# stm32hw03.net
KiCad netlist of a schematic drawn in EAGLE
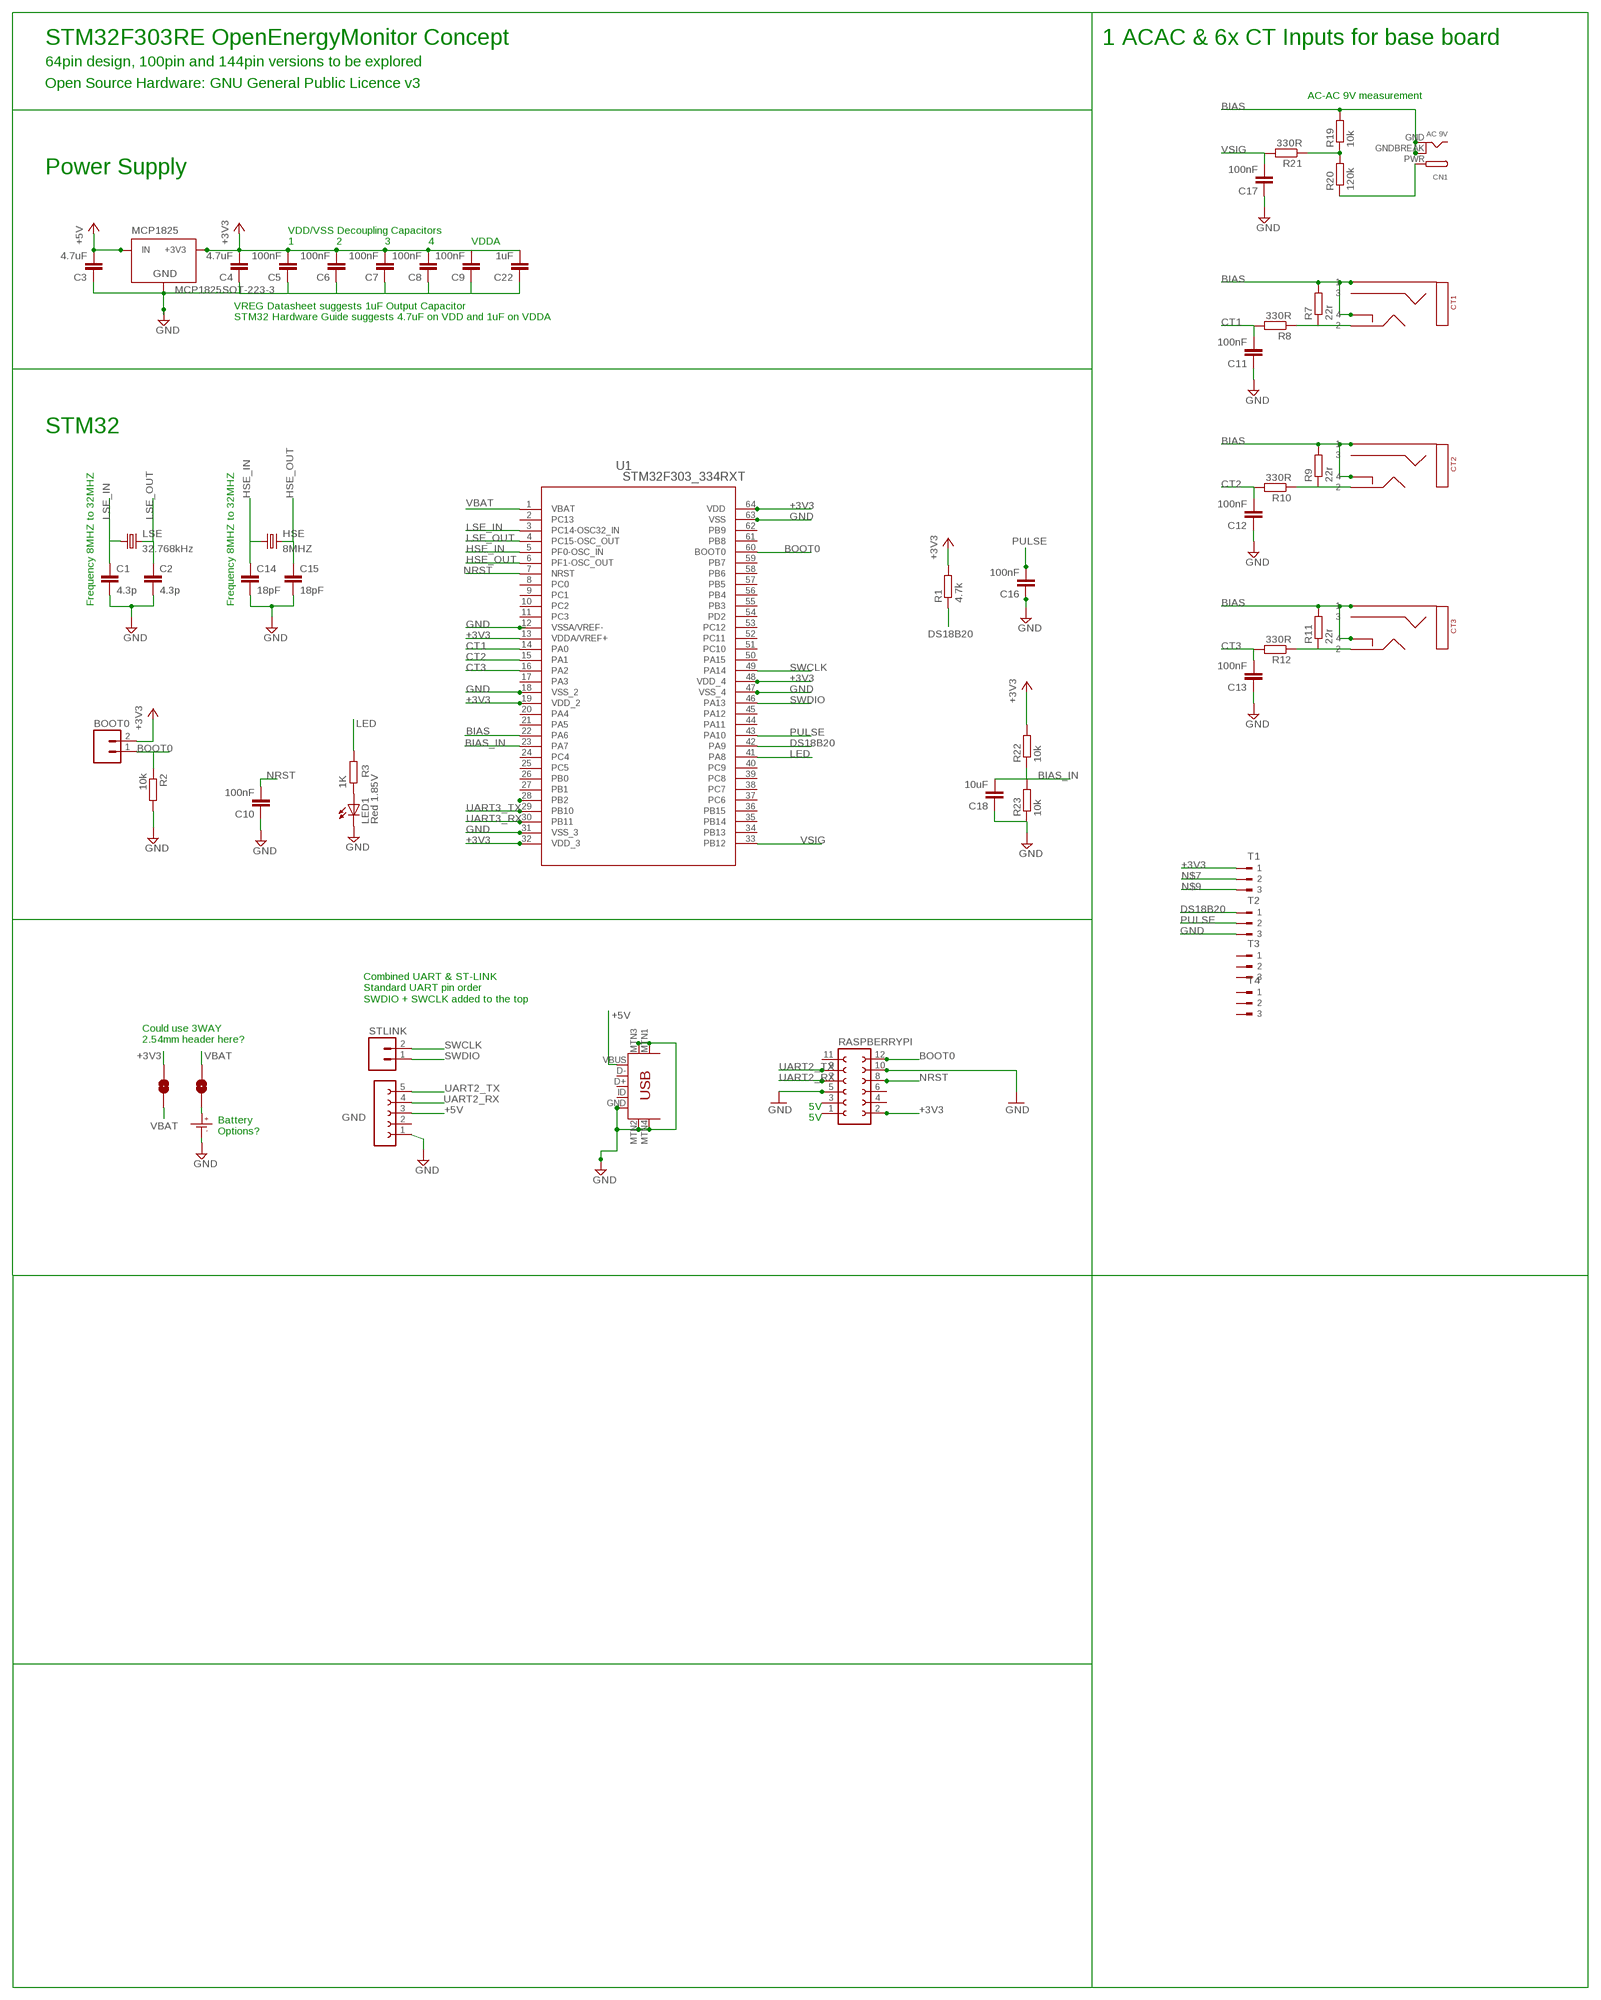
[diagram p0: schematic, sheet 1]

(export (version "E")
  (design (tool "Eeschema 10.0.6"))
  (components
    (comp (ref "3V3")
      (value "SOLDERJUMPERNO")
      (footprint "eagle-import:SJ_2S-NO")
      (libsource (lib "eagle-import") (part "SOLDERJUMPERNO"))
    )
    (comp (ref "BATTERY")
      (value "SOLDERJUMPERNO")
      (footprint "eagle-import:SJ_2S-NO")
      (libsource (lib "eagle-import") (part "SOLDERJUMPERNO"))
    )
    (comp (ref "BOOT0")
      (value "M02PTH")
      (footprint "eagle-import:1X02")
      (libsource (lib "eagle-import") (part "M02PTH"))
    )
    (comp (ref "C1")
      (value "4.3p")
      (footprint "eagle-import:C0603")
      (libsource (lib "eagle-import") (part "C-EUC0603"))
    )
    (comp (ref "C2")
      (value "4.3p")
      (footprint "eagle-import:C0603")
      (libsource (lib "eagle-import") (part "C-EUC0603"))
    )
    (comp (ref "C3")
      (value "4.7uF")
      (footprint "eagle-import:C0603")
      (libsource (lib "eagle-import") (part "C-EUC0603"))
    )
    (comp (ref "C4")
      (value "4.7uF")
      (footprint "eagle-import:C0603")
      (libsource (lib "eagle-import") (part "C-EUC0603"))
    )
    (comp (ref "C5")
      (value "100nF")
      (footprint "eagle-import:C0603")
      (libsource (lib "eagle-import") (part "C-EUC0603"))
    )
    (comp (ref "C6")
      (value "100nF")
      (footprint "eagle-import:C0603")
      (libsource (lib "eagle-import") (part "C-EUC0603"))
    )
    (comp (ref "C7")
      (value "100nF")
      (footprint "eagle-import:C0603")
      (libsource (lib "eagle-import") (part "C-EUC0603"))
    )
    (comp (ref "C8")
      (value "100nF")
      (footprint "eagle-import:C0603")
      (libsource (lib "eagle-import") (part "C-EUC0603"))
    )
    (comp (ref "C9")
      (value "100nF")
      (footprint "eagle-import:C0603")
      (libsource (lib "eagle-import") (part "C-EUC0603"))
    )
    (comp (ref "C10")
      (value "100nF")
      (footprint "eagle-import:C0603")
      (libsource (lib "eagle-import") (part "C-EUC0603"))
    )
    (comp (ref "C11")
      (value "100nF")
      (footprint "eagle-import:C0603")
      (libsource (lib "eagle-import") (part "C-EUC0603"))
    )
    (comp (ref "C12")
      (value "100nF")
      (footprint "eagle-import:C0603")
      (libsource (lib "eagle-import") (part "C-EUC0603"))
    )
    (comp (ref "C13")
      (value "100nF")
      (footprint "eagle-import:C0603")
      (libsource (lib "eagle-import") (part "C-EUC0603"))
    )
    (comp (ref "C14")
      (value "18pF")
      (footprint "eagle-import:C0603")
      (libsource (lib "eagle-import") (part "C-EUC0603"))
    )
    (comp (ref "C15")
      (value "18pF")
      (footprint "eagle-import:C0603")
      (libsource (lib "eagle-import") (part "C-EUC0603"))
    )
    (comp (ref "C16")
      (value "100nF")
      (footprint "eagle-import:C0603")
      (libsource (lib "eagle-import") (part "C-EUC0603"))
    )
    (comp (ref "C17")
      (value "100nF")
      (footprint "eagle-import:C0603")
      (libsource (lib "eagle-import") (part "C-EUC0603"))
    )
    (comp (ref "C18")
      (value "10uF")
      (footprint "eagle-import:C0603")
      (libsource (lib "eagle-import") (part "C-EUC0603"))
    )
    (comp (ref "C22")
      (value "1uF")
      (footprint "eagle-import:C0603")
      (libsource (lib "eagle-import") (part "C-EUC0603"))
    )
    (comp (ref "CN1")
      (value "AC 9V")
      (footprint "eagle-import:DCJACK_2MM_PTH")
      (libsource (lib "eagle-import") (part "DCBARRELPTH"))
    )
    (comp (ref "CR1220")
      (value "CR1220SMD")
      (footprint "eagle-import:CR1220SMD")
      (fields (field (name "MPN") "Harwin S8411-45R"))
      (libsource (lib "eagle-import") (part "CR1220SMD"))
    )
    (comp (ref "CT1")
      (value "STEREO_SMD")
      (footprint "eagle-import:STEREO_SMT")
      (libsource (lib "eagle-import") (part "STEREO_SMD"))
    )
    (comp (ref "CT2")
      (value "STEREO_SMD")
      (footprint "eagle-import:STEREO_SMT")
      (libsource (lib "eagle-import") (part "STEREO_SMD"))
    )
    (comp (ref "CT3")
      (value "STEREO_SMD")
      (footprint "eagle-import:STEREO_SMT")
      (libsource (lib "eagle-import") (part "STEREO_SMD"))
    )
    (comp (ref "GND")
      (value "UART")
      (footprint "eagle-import:FE05-1")
      (libsource (lib "eagle-import") (part "FE05-1"))
    )
    (comp (ref "HSE")
      (value "8MHZ")
      (footprint "eagle-import:CTS406")
      (libsource (lib "eagle-import") (part "CRYSTALCTS406"))
    )
    (comp (ref "LED1")
      (value "Red 1.85V")
      (footprint "eagle-import:CHIP-LED0805")
      (libsource (lib "eagle-import") (part "LEDCHIP-LED0805"))
    )
    (comp (ref "LSE")
      (value "32.768kHz")
      (footprint "eagle-import:MC-306")
      (fields (field (name "MPN") "MC-306 60.0KHZ  100PPM ,12.5PF"))
      (libsource (lib "eagle-import") (part "MC-306"))
    )
    (comp (ref "MCP1825")
      (value "MCP1825SOT-223-3")
      (footprint "eagle-import:SOT-223")
      (libsource (lib "eagle-import") (part "MCP1825SOT-223-3"))
    )
    (comp (ref "R1")
      (value "4.7k")
      (footprint "eagle-import:R0603")
      (libsource (lib "eagle-import") (part "resistor_R-EU_R0603"))
    )
    (comp (ref "R2")
      (value "10k")
      (footprint "eagle-import:R0603")
      (libsource (lib "eagle-import") (part "resistor_R-EU_R0603"))
    )
    (comp (ref "R3")
      (value "1K")
      (footprint "eagle-import:R0603")
      (libsource (lib "eagle-import") (part "R-EU_R0603"))
    )
    (comp (ref "R7")
      (value "22r")
      (footprint "eagle-import:R0603")
      (libsource (lib "eagle-import") (part "resistor_R-EU_R0603"))
    )
    (comp (ref "R8")
      (value "330R")
      (footprint "eagle-import:R0603")
      (libsource (lib "eagle-import") (part "resistor_R-EU_R0603"))
    )
    (comp (ref "R9")
      (value "22r")
      (footprint "eagle-import:R0603")
      (libsource (lib "eagle-import") (part "resistor_R-EU_R0603"))
    )
    (comp (ref "R10")
      (value "330R")
      (footprint "eagle-import:R0603")
      (libsource (lib "eagle-import") (part "resistor_R-EU_R0603"))
    )
    (comp (ref "R11")
      (value "22r")
      (footprint "eagle-import:R0603")
      (libsource (lib "eagle-import") (part "resistor_R-EU_R0603"))
    )
    (comp (ref "R12")
      (value "330R")
      (footprint "eagle-import:R0603")
      (libsource (lib "eagle-import") (part "resistor_R-EU_R0603"))
    )
    (comp (ref "R19")
      (value "10k")
      (footprint "eagle-import:R0603")
      (libsource (lib "eagle-import") (part "resistor_R-EU_R0603"))
    )
    (comp (ref "R20")
      (value "120k")
      (footprint "eagle-import:R0603")
      (libsource (lib "eagle-import") (part "resistor_R-EU_R0603"))
    )
    (comp (ref "R21")
      (value "330R")
      (footprint "eagle-import:R0603")
      (libsource (lib "eagle-import") (part "resistor_R-EU_R0603"))
    )
    (comp (ref "R22")
      (value "10k")
      (footprint "eagle-import:R0603")
      (libsource (lib "eagle-import") (part "resistor_R-EU_R0603"))
    )
    (comp (ref "R23")
      (value "10k")
      (footprint "eagle-import:R0603")
      (libsource (lib "eagle-import") (part "resistor_R-EU_R0603"))
    )
    (comp (ref "RASPBERRYPI")
      (value "FE06-2")
      (footprint "eagle-import:FE06-2")
      (libsource (lib "eagle-import") (part "FE06-2"))
    )
    (comp (ref "STLINK")
      (value "M02PTH")
      (footprint "eagle-import:1X02")
      (libsource (lib "eagle-import") (part "M02PTH"))
    )
    (comp (ref "T1")
      (value "180-3")
      (footprint "eagle-import:180-3")
      (libsource (lib "eagle-import") (part "180-3"))
    )
    (comp (ref "T2")
      (value "180-3")
      (footprint "eagle-import:180-3")
      (libsource (lib "eagle-import") (part "180-3"))
    )
    (comp (ref "T3")
      (value "180-3")
      (footprint "eagle-import:180-3")
      (libsource (lib "eagle-import") (part "180-3"))
    )
    (comp (ref "T4")
      (value "180-3")
      (footprint "eagle-import:180-3")
      (libsource (lib "eagle-import") (part "180-3"))
    )
    (comp (ref "U$10")
      (value "USB-MINIB-5PIN")
      (footprint "eagle-import:USB-MINIB-CISECO")
      (libsource (lib "eagle-import") (part "USB-MINIB-5PIN"))
    )
    (comp (ref "U1")
      (value "STM32F303_334RXT")
      (footprint "eagle-import:LQFP64-10X10MM")
      (fields (field (name "MANUFACTURER_PART_NUMBER") "stm32f303_334rxt"))
      (libsource (lib "eagle-import") (part "STM32F303_334RXT"))
    )
  )
  (nets
    (net (code "1") (name "+3V3") (class "Default")
      (node (ref "3V3") (pin "1") (pinfunction "1_1") (pintype "passive"))
      (node (ref "BOOT0") (pin "2") (pinfunction "2_2") (pintype "passive"))
      (node (ref "C22") (pin "2") (pinfunction "2_2") (pintype "passive"))
      (node (ref "C4") (pin "2") (pinfunction "2_2") (pintype "passive"))
      (node (ref "C5") (pin "2") (pinfunction "2_2") (pintype "passive"))
      (node (ref "C6") (pin "2") (pinfunction "2_2") (pintype "passive"))
      (node (ref "C7") (pin "2") (pinfunction "2_2") (pintype "passive"))
      (node (ref "C8") (pin "2") (pinfunction "2_2") (pintype "passive"))
      (node (ref "C9") (pin "2") (pinfunction "2_2") (pintype "passive"))
      (node (ref "MCP1825") (pin "3") (pinfunction "+3V3_3") (pintype "power_in"))
      (node (ref "R1") (pin "2") (pinfunction "2_2") (pintype "passive"))
      (node (ref "R22") (pin "2") (pinfunction "2_2") (pintype "passive"))
      (node (ref "RASPBERRYPI") (pin "2") (pinfunction "2_2") (pintype "passive"))
      (node (ref "T1") (pin "1") (pinfunction "1_1") (pintype "passive"))
      (node (ref "U1") (pin "13") (pinfunction "VDDA/VREF+_13") (pintype "power_in"))
      (node (ref "U1") (pin "19") (pinfunction "VDD_2_19") (pintype "power_in"))
      (node (ref "U1") (pin "32") (pinfunction "VDD_3_32") (pintype "power_in"))
      (node (ref "U1") (pin "48") (pinfunction "VDD_4_48") (pintype "power_in"))
      (node (ref "U1") (pin "64") (pinfunction "VDD_64") (pintype "power_in"))
    )
    (net (code "2") (name "+5V") (class "Default")
      (node (ref "C3") (pin "2") (pinfunction "2_2") (pintype "passive"))
      (node (ref "GND") (pin "3") (pinfunction "3_3") (pintype "passive"))
      (node (ref "MCP1825") (pin "1") (pinfunction "IN_1") (pintype "power_in"))
      (node (ref "U$10") (pin "VBUS") (pinfunction "VBUS_VBUS") (pintype "bidirectional"))
    )
    (net (code "3") (name "/BIAS") (class "Default")
      (node (ref "CN1") (pin "GND") (pinfunction "GND_GND") (pintype "power_in"))
      (node (ref "CN1") (pin "GNDBREAK") (pinfunction "GNDBREAK_GNDBREAK") (pintype "power_in"))
      (node (ref "CT1") (pin "P$1") (pinfunction "1_P$1") (pintype "bidirectional"))
      (node (ref "CT1") (pin "P$4") (pinfunction "4_P$4") (pintype "bidirectional"))
      (node (ref "CT2") (pin "P$1") (pinfunction "1_P$1") (pintype "bidirectional"))
      (node (ref "CT2") (pin "P$4") (pinfunction "4_P$4") (pintype "bidirectional"))
      (node (ref "CT3") (pin "P$1") (pinfunction "1_P$1") (pintype "bidirectional"))
      (node (ref "CT3") (pin "P$4") (pinfunction "4_P$4") (pintype "bidirectional"))
      (node (ref "R11") (pin "2") (pinfunction "2_2") (pintype "passive"))
      (node (ref "R19") (pin "2") (pinfunction "2_2") (pintype "passive"))
      (node (ref "R7") (pin "2") (pinfunction "2_2") (pintype "passive"))
      (node (ref "R9") (pin "2") (pinfunction "2_2") (pintype "passive"))
      (node (ref "U1") (pin "22") (pinfunction "PA6_22") (pintype "bidirectional"))
    )
    (net (code "4") (name "/BIAS_IN") (class "Default")
      (node (ref "C18") (pin "2") (pinfunction "2_2") (pintype "passive"))
      (node (ref "R22") (pin "1") (pinfunction "1_1") (pintype "passive"))
      (node (ref "R23") (pin "2") (pinfunction "2_2") (pintype "passive"))
      (node (ref "U1") (pin "23") (pinfunction "PA7_23") (pintype "bidirectional"))
    )
    (net (code "5") (name "/BOOT0") (class "Default")
      (node (ref "BOOT0") (pin "1") (pinfunction "1_1") (pintype "passive"))
      (node (ref "R2") (pin "1") (pinfunction "1_1") (pintype "passive"))
      (node (ref "RASPBERRYPI") (pin "12") (pinfunction "12_12") (pintype "passive"))
      (node (ref "U1") (pin "60") (pinfunction "BOOT0_60") (pintype "input"))
    )
    (net (code "6") (name "/CT1") (class "Default")
      (node (ref "C11") (pin "2") (pinfunction "2_2") (pintype "passive"))
      (node (ref "R8") (pin "2") (pinfunction "2_2") (pintype "passive"))
      (node (ref "U1") (pin "14") (pinfunction "PA0_14") (pintype "bidirectional"))
    )
    (net (code "7") (name "/CT2") (class "Default")
      (node (ref "C12") (pin "2") (pinfunction "2_2") (pintype "passive"))
      (node (ref "R10") (pin "2") (pinfunction "2_2") (pintype "passive"))
      (node (ref "U1") (pin "15") (pinfunction "PA1_15") (pintype "bidirectional"))
    )
    (net (code "8") (name "/CT3") (class "Default")
      (node (ref "C13") (pin "2") (pinfunction "2_2") (pintype "passive"))
      (node (ref "R12") (pin "2") (pinfunction "2_2") (pintype "passive"))
      (node (ref "U1") (pin "16") (pinfunction "PA2_16") (pintype "bidirectional"))
    )
    (net (code "9") (name "/DS18B20") (class "Default")
      (node (ref "R1") (pin "1") (pinfunction "1_1") (pintype "passive"))
      (node (ref "T2") (pin "1") (pinfunction "1_1") (pintype "passive"))
      (node (ref "U1") (pin "42") (pinfunction "PA9_42") (pintype "bidirectional"))
    )
    (net (code "10") (name "/HSE_IN") (class "Default")
      (node (ref "C14") (pin "1") (pinfunction "1_1") (pintype "passive"))
      (node (ref "HSE") (pin "1") (pinfunction "1_1") (pintype "passive"))
      (node (ref "U1") (pin "5") (pinfunction "PF0-OSC_IN_5") (pintype "bidirectional"))
    )
    (net (code "11") (name "/HSE_OUT") (class "Default")
      (node (ref "C15") (pin "1") (pinfunction "1_1") (pintype "passive"))
      (node (ref "HSE") (pin "3") (pinfunction "2_3") (pintype "passive"))
      (node (ref "U1") (pin "6") (pinfunction "PF1-OSC_OUT_6") (pintype "bidirectional"))
    )
    (net (code "12") (name "/LED") (class "Default")
      (node (ref "R3") (pin "2") (pinfunction "2_2") (pintype "passive"))
      (node (ref "U1") (pin "41") (pinfunction "PA8_41") (pintype "bidirectional"))
    )
    (net (code "13") (name "/LSE_IN") (class "Default")
      (node (ref "C1") (pin "1") (pinfunction "1_1") (pintype "passive"))
      (node (ref "LSE") (pin "1") (pinfunction "1_1") (pintype "passive"))
      (node (ref "U1") (pin "3") (pinfunction "PC14-OSC32_IN_3") (pintype "bidirectional"))
    )
    (net (code "14") (name "/LSE_OUT") (class "Default")
      (node (ref "C2") (pin "1") (pinfunction "1_1") (pintype "passive"))
      (node (ref "LSE") (pin "4") (pinfunction "2_4") (pintype "passive"))
      (node (ref "U1") (pin "4") (pinfunction "PC15-OSC_OUT_4") (pintype "bidirectional"))
    )
    (net (code "15") (name "/N$7") (class "Default")
      (node (ref "T1") (pin "2") (pinfunction "2_2") (pintype "passive"))
    )
    (net (code "16") (name "/N$9") (class "Default")
      (node (ref "T1") (pin "3") (pinfunction "3_3") (pintype "passive"))
    )
    (net (code "17") (name "/NRST") (class "Default")
      (node (ref "C10") (pin "2") (pinfunction "2_2") (pintype "passive"))
      (node (ref "RASPBERRYPI") (pin "8") (pinfunction "8_8") (pintype "passive"))
      (node (ref "U1") (pin "7") (pinfunction "NRST_7") (pintype "bidirectional"))
    )
    (net (code "18") (name "/PULSE") (class "Default")
      (node (ref "C16") (pin "2") (pinfunction "2_2") (pintype "passive"))
      (node (ref "T2") (pin "2") (pinfunction "2_2") (pintype "passive"))
      (node (ref "U1") (pin "43") (pinfunction "PA10_43") (pintype "bidirectional"))
    )
    (net (code "19") (name "/SWCLK") (class "Default")
      (node (ref "STLINK") (pin "2") (pinfunction "2_2") (pintype "passive"))
      (node (ref "U1") (pin "49") (pinfunction "PA14_49") (pintype "bidirectional"))
    )
    (net (code "20") (name "/SWDIO") (class "Default")
      (node (ref "STLINK") (pin "1") (pinfunction "1_1") (pintype "passive"))
      (node (ref "U1") (pin "46") (pinfunction "PA13_46") (pintype "bidirectional"))
    )
    (net (code "21") (name "/UART2_RX") (class "Default")
      (node (ref "GND") (pin "4") (pinfunction "4_4") (pintype "passive"))
      (node (ref "RASPBERRYPI") (pin "7") (pinfunction "7_7") (pintype "passive"))
    )
    (net (code "22") (name "/UART2_TX") (class "Default")
      (node (ref "GND") (pin "5") (pinfunction "5_5") (pintype "passive"))
      (node (ref "RASPBERRYPI") (pin "9") (pinfunction "9_9") (pintype "passive"))
    )
    (net (code "23") (name "/UART3_RX") (class "Default")
      (node (ref "U1") (pin "30") (pinfunction "PB11_30") (pintype "bidirectional"))
    )
    (net (code "24") (name "/UART3_TX") (class "Default")
      (node (ref "U1") (pin "29") (pinfunction "PB10_29") (pintype "bidirectional"))
    )
    (net (code "25") (name "/VBAT") (class "Default")
      (node (ref "3V3") (pin "2") (pinfunction "2_2") (pintype "passive"))
      (node (ref "BATTERY") (pin "1") (pinfunction "1_1") (pintype "passive"))
      (node (ref "U1") (pin "1") (pinfunction "VBAT_1") (pintype "power_in"))
    )
    (net (code "26") (name "/VSIG") (class "Default")
      (node (ref "C17") (pin "2") (pinfunction "2_2") (pintype "passive"))
      (node (ref "R21") (pin "2") (pinfunction "2_2") (pintype "passive"))
      (node (ref "U1") (pin "33") (pinfunction "PB12_33") (pintype "bidirectional"))
    )
    (net (code "27") (name "GND") (class "Default")
      (node (ref "C1") (pin "2") (pinfunction "2_2") (pintype "passive"))
      (node (ref "C10") (pin "1") (pinfunction "1_1") (pintype "passive"))
      (node (ref "C11") (pin "1") (pinfunction "1_1") (pintype "passive"))
      (node (ref "C12") (pin "1") (pinfunction "1_1") (pintype "passive"))
      (node (ref "C13") (pin "1") (pinfunction "1_1") (pintype "passive"))
      (node (ref "C14") (pin "2") (pinfunction "2_2") (pintype "passive"))
      (node (ref "C15") (pin "2") (pinfunction "2_2") (pintype "passive"))
      (node (ref "C16") (pin "1") (pinfunction "1_1") (pintype "passive"))
      (node (ref "C17") (pin "1") (pinfunction "1_1") (pintype "passive"))
      (node (ref "C18") (pin "1") (pinfunction "1_1") (pintype "passive"))
      (node (ref "C2") (pin "2") (pinfunction "2_2") (pintype "passive"))
      (node (ref "C22") (pin "1") (pinfunction "1_1") (pintype "passive"))
      (node (ref "C3") (pin "1") (pinfunction "1_1") (pintype "passive"))
      (node (ref "C4") (pin "1") (pinfunction "1_1") (pintype "passive"))
      (node (ref "C5") (pin "1") (pinfunction "1_1") (pintype "passive"))
      (node (ref "C6") (pin "1") (pinfunction "1_1") (pintype "passive"))
      (node (ref "C7") (pin "1") (pinfunction "1_1") (pintype "passive"))
      (node (ref "C8") (pin "1") (pinfunction "1_1") (pintype "passive"))
      (node (ref "C9") (pin "1") (pinfunction "1_1") (pintype "passive"))
      (node (ref "CR1220") (pin "P-") (pinfunction "P$-_P-") (pintype "bidirectional"))
      (node (ref "GND") (pin "1") (pinfunction "1_1") (pintype "passive"))
      (node (ref "LED1") (pin "C") (pinfunction "C_C") (pintype "passive"))
      (node (ref "MCP1825") (pin "2") (pinfunction "GND_2") (pintype "power_in"))
      (node (ref "R2") (pin "2") (pinfunction "2_2") (pintype "passive"))
      (node (ref "R23") (pin "1") (pinfunction "1_1") (pintype "passive"))
      (node (ref "RASPBERRYPI") (pin "10") (pinfunction "10_10") (pintype "passive"))
      (node (ref "RASPBERRYPI") (pin "5") (pinfunction "5_5") (pintype "passive"))
      (node (ref "T2") (pin "3") (pinfunction "3_3") (pintype "passive"))
      (node (ref "U$10") (pin "GND") (pinfunction "GND_GND") (pintype "bidirectional"))
      (node (ref "U$10") (pin "MTN1") (pinfunction "MTN2_MTN1") (pintype "bidirectional"))
      (node (ref "U$10") (pin "MTN2") (pinfunction "MTN3_MTN2") (pintype "bidirectional"))
      (node (ref "U$10") (pin "MTN3") (pinfunction "MTN1_MTN3") (pintype "bidirectional"))
      (node (ref "U$10") (pin "MTN4") (pinfunction "MTN4_MTN4") (pintype "bidirectional"))
      (node (ref "U1") (pin "12") (pinfunction "VSSA/VREF-_12") (pintype "power_in"))
      (node (ref "U1") (pin "18") (pinfunction "VSS_2_18") (pintype "power_in"))
      (node (ref "U1") (pin "31") (pinfunction "VSS_3_31") (pintype "power_in"))
      (node (ref "U1") (pin "47") (pinfunction "VSS_4_47") (pintype "power_in"))
      (node (ref "U1") (pin "63") (pinfunction "VSS_63") (pintype "power_in"))
    )
    (net (code "28") (name "Net-(CN1-PadPWR)") (class "Default")
      (node (ref "CN1") (pin "PWR") (pinfunction "PWR_PWR") (pintype "power_in"))
      (node (ref "R20") (pin "1") (pinfunction "1_1") (pintype "passive"))
    )
    (net (code "29") (name "Net-(CR1220-P$+)") (class "Default")
      (node (ref "BATTERY") (pin "2") (pinfunction "2_2") (pintype "passive"))
      (node (ref "CR1220") (pin "P+") (pinfunction "P$+_P+") (pintype "bidirectional"))
    )
    (net (code "30") (name "Net-(CT1-2)") (class "Default")
      (node (ref "CT1") (pin "P$2") (pinfunction "2_P$2") (pintype "bidirectional"))
      (node (ref "R7") (pin "1") (pinfunction "1_1") (pintype "passive"))
      (node (ref "R8") (pin "1") (pinfunction "1_1") (pintype "passive"))
    )
    (net (code "31") (name "Net-(CT2-2)") (class "Default")
      (node (ref "CT2") (pin "P$2") (pinfunction "2_P$2") (pintype "bidirectional"))
      (node (ref "R10") (pin "1") (pinfunction "1_1") (pintype "passive"))
      (node (ref "R9") (pin "1") (pinfunction "1_1") (pintype "passive"))
    )
    (net (code "32") (name "Net-(CT3-2)") (class "Default")
      (node (ref "CT3") (pin "P$2") (pinfunction "2_P$2") (pintype "bidirectional"))
      (node (ref "R11") (pin "1") (pinfunction "1_1") (pintype "passive"))
      (node (ref "R12") (pin "1") (pinfunction "1_1") (pintype "passive"))
    )
    (net (code "33") (name "Net-(LED1-PadA)") (class "Default")
      (node (ref "LED1") (pin "A") (pinfunction "A_A") (pintype "passive"))
      (node (ref "R3") (pin "1") (pinfunction "1_1") (pintype "passive"))
    )
    (net (code "34") (name "Net-(R19-Pad1)") (class "Default")
      (node (ref "R19") (pin "1") (pinfunction "1_1") (pintype "passive"))
      (node (ref "R20") (pin "2") (pinfunction "2_2") (pintype "passive"))
      (node (ref "R21") (pin "1") (pinfunction "1_1") (pintype "passive"))
    )
    (net (code "35") (name "unconnected-(CT1-3-PadP$3)") (class "Default")
      (node (ref "CT1") (pin "P$3") (pinfunction "3_P$3") (pintype "bidirectional"))
    )
    (net (code "36") (name "unconnected-(CT2-3-PadP$3)") (class "Default")
      (node (ref "CT2") (pin "P$3") (pinfunction "3_P$3") (pintype "bidirectional"))
    )
    (net (code "37") (name "unconnected-(CT3-3-PadP$3)") (class "Default")
      (node (ref "CT3") (pin "P$3") (pinfunction "3_P$3") (pintype "bidirectional"))
    )
    (net (code "38") (name "unconnected-(GND-Pad2)") (class "Default")
      (node (ref "GND") (pin "2") (pinfunction "2_2") (pintype "passive"))
    )
    (net (code "39") (name "unconnected-(RASPBERRYPI-Pad1)") (class "Default")
      (node (ref "RASPBERRYPI") (pin "1") (pinfunction "1_1") (pintype "passive"))
    )
    (net (code "40") (name "unconnected-(RASPBERRYPI-Pad3)") (class "Default")
      (node (ref "RASPBERRYPI") (pin "3") (pinfunction "3_3") (pintype "passive"))
    )
    (net (code "41") (name "unconnected-(RASPBERRYPI-Pad4)") (class "Default")
      (node (ref "RASPBERRYPI") (pin "4") (pinfunction "4_4") (pintype "passive"))
    )
    (net (code "42") (name "unconnected-(RASPBERRYPI-Pad6)") (class "Default")
      (node (ref "RASPBERRYPI") (pin "6") (pinfunction "6_6") (pintype "passive"))
    )
    (net (code "43") (name "unconnected-(RASPBERRYPI-Pad11)") (class "Default")
      (node (ref "RASPBERRYPI") (pin "11") (pinfunction "11_11") (pintype "passive"))
    )
    (net (code "44") (name "unconnected-(T3-Pad1)") (class "Default")
      (node (ref "T3") (pin "1") (pinfunction "1_1") (pintype "passive"))
    )
    (net (code "45") (name "unconnected-(T3-Pad2)") (class "Default")
      (node (ref "T3") (pin "2") (pinfunction "2_2") (pintype "passive"))
    )
    (net (code "46") (name "unconnected-(T3-Pad3)") (class "Default")
      (node (ref "T3") (pin "3") (pinfunction "3_3") (pintype "passive"))
    )
    (net (code "47") (name "unconnected-(T4-Pad1)") (class "Default")
      (node (ref "T4") (pin "1") (pinfunction "1_1") (pintype "passive"))
    )
    (net (code "48") (name "unconnected-(T4-Pad2)") (class "Default")
      (node (ref "T4") (pin "2") (pinfunction "2_2") (pintype "passive"))
    )
    (net (code "49") (name "unconnected-(T4-Pad3)") (class "Default")
      (node (ref "T4") (pin "3") (pinfunction "3_3") (pintype "passive"))
    )
    (net (code "50") (name "unconnected-(U$10-PadD+)") (class "Default")
      (node (ref "U$10") (pin "D+") (pinfunction "D+_D+") (pintype "bidirectional"))
    )
    (net (code "51") (name "unconnected-(U$10-PadD-)") (class "Default")
      (node (ref "U$10") (pin "D-") (pinfunction "D-_D-") (pintype "bidirectional"))
    )
    (net (code "52") (name "unconnected-(U$10-PadID)") (class "Default")
      (node (ref "U$10") (pin "ID") (pinfunction "ID_ID") (pintype "bidirectional"))
    )
    (net (code "53") (name "unconnected-(U1-PA3-Pad17)") (class "Default")
      (node (ref "U1") (pin "17") (pinfunction "PA3_17") (pintype "bidirectional"))
    )
    (net (code "54") (name "unconnected-(U1-PA4-Pad20)") (class "Default")
      (node (ref "U1") (pin "20") (pinfunction "PA4_20") (pintype "bidirectional"))
    )
    (net (code "55") (name "unconnected-(U1-PA5-Pad21)") (class "Default")
      (node (ref "U1") (pin "21") (pinfunction "PA5_21") (pintype "bidirectional"))
    )
    (net (code "56") (name "unconnected-(U1-PA11-Pad44)") (class "Default")
      (node (ref "U1") (pin "44") (pinfunction "PA11_44") (pintype "bidirectional"))
    )
    (net (code "57") (name "unconnected-(U1-PA12-Pad45)") (class "Default")
      (node (ref "U1") (pin "45") (pinfunction "PA12_45") (pintype "bidirectional"))
    )
    (net (code "58") (name "unconnected-(U1-PA15-Pad50)") (class "Default")
      (node (ref "U1") (pin "50") (pinfunction "PA15_50") (pintype "bidirectional"))
    )
    (net (code "59") (name "unconnected-(U1-PB0-Pad26)") (class "Default")
      (node (ref "U1") (pin "26") (pinfunction "PB0_26") (pintype "bidirectional"))
    )
    (net (code "60") (name "unconnected-(U1-PB1-Pad27)") (class "Default")
      (node (ref "U1") (pin "27") (pinfunction "PB1_27") (pintype "bidirectional"))
    )
    (net (code "61") (name "unconnected-(U1-PB2-Pad28)") (class "Default")
      (node (ref "U1") (pin "28") (pinfunction "PB2_28") (pintype "bidirectional"))
    )
    (net (code "62") (name "unconnected-(U1-PB3-Pad55)") (class "Default")
      (node (ref "U1") (pin "55") (pinfunction "PB3_55") (pintype "bidirectional"))
    )
    (net (code "63") (name "unconnected-(U1-PB4-Pad56)") (class "Default")
      (node (ref "U1") (pin "56") (pinfunction "PB4_56") (pintype "bidirectional"))
    )
    (net (code "64") (name "unconnected-(U1-PB5-Pad57)") (class "Default")
      (node (ref "U1") (pin "57") (pinfunction "PB5_57") (pintype "bidirectional"))
    )
    (net (code "65") (name "unconnected-(U1-PB6-Pad58)") (class "Default")
      (node (ref "U1") (pin "58") (pinfunction "PB6_58") (pintype "bidirectional"))
    )
    (net (code "66") (name "unconnected-(U1-PB7-Pad59)") (class "Default")
      (node (ref "U1") (pin "59") (pinfunction "PB7_59") (pintype "bidirectional"))
    )
    (net (code "67") (name "unconnected-(U1-PB8-Pad61)") (class "Default")
      (node (ref "U1") (pin "61") (pinfunction "PB8_61") (pintype "bidirectional"))
    )
    (net (code "68") (name "unconnected-(U1-PB9-Pad62)") (class "Default")
      (node (ref "U1") (pin "62") (pinfunction "PB9_62") (pintype "bidirectional"))
    )
    (net (code "69") (name "unconnected-(U1-PB13-Pad34)") (class "Default")
      (node (ref "U1") (pin "34") (pinfunction "PB13_34") (pintype "bidirectional"))
    )
    (net (code "70") (name "unconnected-(U1-PB14-Pad35)") (class "Default")
      (node (ref "U1") (pin "35") (pinfunction "PB14_35") (pintype "bidirectional"))
    )
    (net (code "71") (name "unconnected-(U1-PB15-Pad36)") (class "Default")
      (node (ref "U1") (pin "36") (pinfunction "PB15_36") (pintype "bidirectional"))
    )
    (net (code "72") (name "unconnected-(U1-PC0-Pad8)") (class "Default")
      (node (ref "U1") (pin "8") (pinfunction "PC0_8") (pintype "bidirectional"))
    )
    (net (code "73") (name "unconnected-(U1-PC1-Pad9)") (class "Default")
      (node (ref "U1") (pin "9") (pinfunction "PC1_9") (pintype "bidirectional"))
    )
    (net (code "74") (name "unconnected-(U1-PC2-Pad10)") (class "Default")
      (node (ref "U1") (pin "10") (pinfunction "PC2_10") (pintype "bidirectional"))
    )
    (net (code "75") (name "unconnected-(U1-PC3-Pad11)") (class "Default")
      (node (ref "U1") (pin "11") (pinfunction "PC3_11") (pintype "bidirectional"))
    )
    (net (code "76") (name "unconnected-(U1-PC4-Pad24)") (class "Default")
      (node (ref "U1") (pin "24") (pinfunction "PC4_24") (pintype "bidirectional"))
    )
    (net (code "77") (name "unconnected-(U1-PC5-Pad25)") (class "Default")
      (node (ref "U1") (pin "25") (pinfunction "PC5_25") (pintype "bidirectional"))
    )
    (net (code "78") (name "unconnected-(U1-PC6-Pad37)") (class "Default")
      (node (ref "U1") (pin "37") (pinfunction "PC6_37") (pintype "bidirectional"))
    )
    (net (code "79") (name "unconnected-(U1-PC7-Pad38)") (class "Default")
      (node (ref "U1") (pin "38") (pinfunction "PC7_38") (pintype "bidirectional"))
    )
    (net (code "80") (name "unconnected-(U1-PC8-Pad39)") (class "Default")
      (node (ref "U1") (pin "39") (pinfunction "PC8_39") (pintype "bidirectional"))
    )
    (net (code "81") (name "unconnected-(U1-PC9-Pad40)") (class "Default")
      (node (ref "U1") (pin "40") (pinfunction "PC9_40") (pintype "bidirectional"))
    )
    (net (code "82") (name "unconnected-(U1-PC10-Pad51)") (class "Default")
      (node (ref "U1") (pin "51") (pinfunction "PC10_51") (pintype "bidirectional"))
    )
    (net (code "83") (name "unconnected-(U1-PC11-Pad52)") (class "Default")
      (node (ref "U1") (pin "52") (pinfunction "PC11_52") (pintype "bidirectional"))
    )
    (net (code "84") (name "unconnected-(U1-PC12-Pad53)") (class "Default")
      (node (ref "U1") (pin "53") (pinfunction "PC12_53") (pintype "bidirectional"))
    )
    (net (code "85") (name "unconnected-(U1-PC13-Pad2)") (class "Default")
      (node (ref "U1") (pin "2") (pinfunction "PC13_2") (pintype "bidirectional"))
    )
    (net (code "86") (name "unconnected-(U1-PD2-Pad54)") (class "Default")
      (node (ref "U1") (pin "54") (pinfunction "PD2_54") (pintype "bidirectional"))
    )
  )
)
